# Optical_RX_TX_1-14.net
KiCad netlist of a schematic drawn in Altium Designer
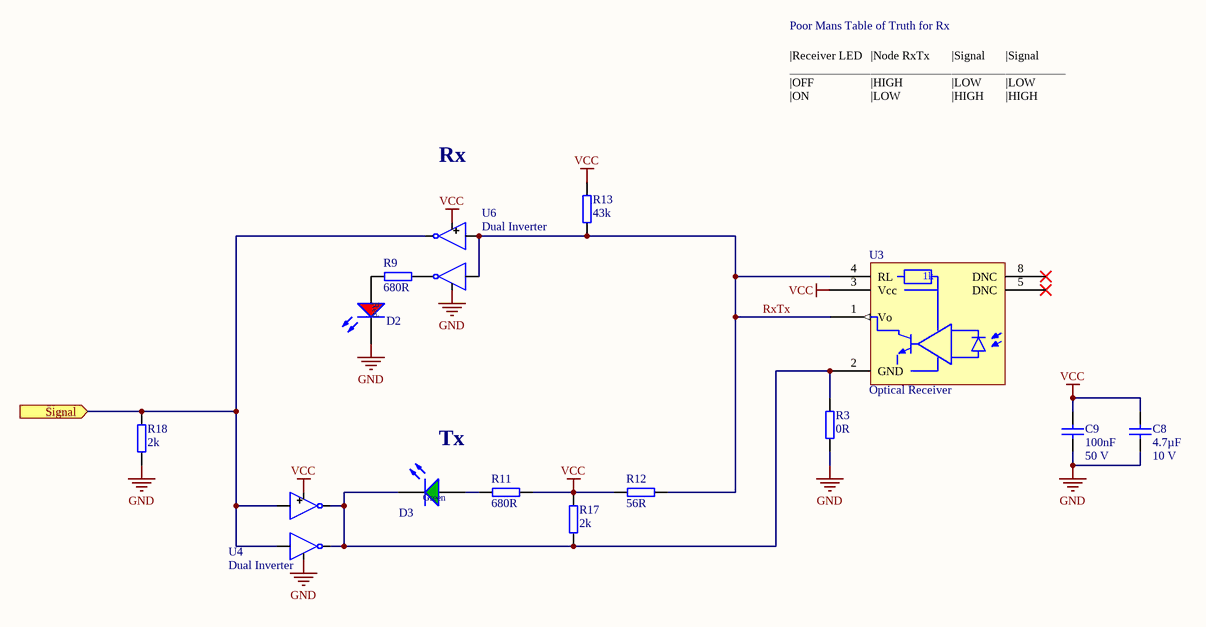
[diagram p0: Optical_RX_TX_1-14.SchDoc]

(export (version "E")
  (design (tool "Eeschema 10.0.6"))
  (components
    (comp (ref "C8")
      (value "4.7µF")
      (footprint "CAP_2012X06N")
      (description "CAP 0805 (2012 Metric) SMD")
      (fields
        (field (name "TOLERANCE") "±10%")
        (field (name "MF") "Taiyo Yuden")
        (field (name "VOLTAGE") "10 V")
        (field (name "CREATED") "2018_09_06_AGeiger")
      )
      (libsource (lib "UZOhm_Optical") (part "C_0805"))
    )
    (comp (ref "C9")
      (value "100nF")
      (footprint "C_0603(1608)100_L")
      (description "CAP 0603 (1608 Metric) SMD")
      (fields
        (field (name "TOLERANCE") "±5%")
        (field (name "LCSC PART #") "C14663")
        (field (name "RATED VOLTAGE") "50 V")
        (field (name "CREATED") "2018_09_06_AGeiger")
      )
      (libsource (lib "UZOhm_Optical") (part "C_0603"))
    )
    (comp (ref "D2")
      (value "150060RS75000")
      (footprint "WL-SMCW_0603")
      (description "WL-SMCW SMD Mono-color Chip LED Waterclear, size 0603, Red, 2 V, 140°")
      (fields
        (field (name "MF") "Wuerth Elektronik")
        (field (name "LCSC PART #") "C2286")
        (field (name "CREATED") "2018_09_06_AGeiger")
      )
      (libsource (lib "UZOhm_Optical") (part "LED_Red_0603"))
    )
    (comp (ref "D3")
      (value "150060GS75000")
      (footprint "WL-SMCW_0603")
      (description "WL-SMCW SMD Mono-color Chip LED Waterclear, size 0603, Green, 3.2 V, 140°")
      (fields
        (field (name "MF") "Wuerth Elektronik")
        (field (name "LCSC PART #") "C72043")
        (field (name "CREATED") "2018_09_06_AGeiger")
      )
      (libsource (lib "UZOhm_Optical") (part "LED_Green_0603"))
    )
    (comp (ref "R3")
      (value "0R")
      (footprint "R_0603_N")
      (description "SMD Resistor 0603")
      (fields
        (field (name "TOLERANCE") "1%")
        (field (name "VOLTAGE") "75V")
        (field (name "CREATED") "2018_09_06_AGeiger")
      )
      (libsource (lib "UZOhm_Optical") (part "R_0603"))
    )
    (comp (ref "R9")
      (value "680R")
      (footprint "R_0603_N")
      (description "SMD Resistor 0603")
      (fields
        (field (name "TOLERANCE") "1%")
        (field (name "VOLTAGE") "75V")
        (field (name "CREATED") "2018_09_06_AGeiger")
      )
      (libsource (lib "UZOhm_Optical") (part "R_0603"))
    )
    (comp (ref "R11")
      (value "680R")
      (footprint "R_0603_N")
      (description "SMD Resistor 0603")
      (fields
        (field (name "TOLERANCE") "1%")
        (field (name "VOLTAGE") "75V")
        (field (name "CREATED") "2018_09_06_AGeiger")
      )
      (libsource (lib "UZOhm_Optical") (part "R_0603"))
    )
    (comp (ref "R12")
      (value "56R")
      (footprint "RES_2012X06N")
      (description "SMD Resistor 0805")
      (fields (field (name "MF") "Bourns") (field (name "MPN") "CR0805-FX-1200ELF"))
      (libsource (lib "UZOhm_Optical") (part "R_0805"))
    )
    (comp (ref "R13")
      (value "43k")
      (footprint "R_0603_N")
      (description "SMD Resistor 0603")
      (fields
        (field (name "TOLERANCE") "1%")
        (field (name "VOLTAGE") "50V")
        (field (name "CREATED") "2018_09_06_AGeiger")
      )
      (libsource (lib "UZOhm_Optical") (part "R_0603_JLC"))
    )
    (comp (ref "R17")
      (value "2k")
      (footprint "R_0603_N")
      (description "SMD Resistor 0603")
      (fields
        (field (name "TOLERANCE") "1%")
        (field (name "VOLTAGE") "75 V")
        (field (name "CREATED") "2018_09_06_AGeiger")
      )
      (libsource (lib "UZOhm_Optical") (part "R_0603"))
    )
    (comp (ref "R18")
      (value "2k")
      (footprint "R_0603_N")
      (description "SMD Resistor 0603")
      (fields
        (field (name "TOLERANCE") "1%")
        (field (name "VOLTAGE") "75 V")
        (field (name "CREATED") "2018_09_06_AGeiger")
      )
      (libsource (lib "UZOhm_Optical") (part "R_0603"))
    )
    (comp (ref "U3")
      (value "Optical Receiver")
      (footprint "HFBRx5XX")
      (description "Fibre Optic Receivers, LINK HORIZ 5MBd RC VR RoHS")
      (fields
        (field (name "MF") "Boadcom/Avago")
        (field (name "MPN") "HFBR-2521Z")
        (field (name "CREATED") "2019_04_09_Kreppel")
      )
      (libsource (lib "UZOhm_Optical") (part "HFBR-2528Z"))
    )
    (comp (ref "U4")
      (value "Dual Inverter")
      (footprint "SN74LVC2GU04DCKR")
      (description "This dual inverter is designed for 1.65-V to 5.5-V VCC\r\noperation.")
      (fields (field (name "LCSC PART #") "C116660"))
      (libsource (lib "UZOhm_Optical") (part "SN74LVC2GU04DCKR"))
    )
    (comp (ref "U6")
      (value "Dual Inverter")
      (footprint "SN74LVC2GU04DCKR")
      (description "This dual inverter is designed for 1.65-V to 5.5-V VCC\r\noperation.")
      (fields (field (name "LCSC PART #") "C116660"))
      (libsource (lib "UZOhm_Optical") (part "SN74LVC2GU04DCKR"))
    )
  )
  (nets
    (net (code "1") (name "/RxTx") (class "Default")
      (node (ref "R12") (pin "2") (pintype "passive"))
      (node (ref "R13") (pin "2") (pinfunction "2_2") (pintype "passive"))
      (node (ref "U3") (pin "1") (pinfunction "Vo_1") (pintype "output"))
      (node (ref "U3") (pin "4") (pinfunction "RL_4") (pintype "passive"))
      (node (ref "U6") (pin "1") (pinfunction "IN1_1") (pintype "passive"))
      (node (ref "U6") (pin "3") (pinfunction "IN2_3") (pintype "passive"))
    )
    (net (code "2") (name "/Signal") (class "Default")
      (node (ref "R18") (pin "2") (pinfunction "2_2") (pintype "passive"))
      (node (ref "U4") (pin "1") (pinfunction "IN1_1") (pintype "passive"))
      (node (ref "U4") (pin "3") (pinfunction "IN2_3") (pintype "passive"))
      (node (ref "U6") (pin "6") (pinfunction "OUT2_6") (pintype "passive"))
    )
    (net (code "3") (name "GND") (class "Default")
      (node (ref "C8") (pin "2") (pinfunction "2_2") (pintype "passive"))
      (node (ref "C9") (pin "2") (pinfunction "2_2") (pintype "passive"))
      (node (ref "D2") (pin "1") (pinfunction "K_1") (pintype "passive"))
      (node (ref "R18") (pin "1") (pinfunction "1_1") (pintype "passive"))
      (node (ref "R3") (pin "2") (pinfunction "2_2") (pintype "passive"))
      (node (ref "U4") (pin "2") (pinfunction "GND_2") (pintype "passive"))
      (node (ref "U6") (pin "2") (pinfunction "GND_2") (pintype "passive"))
    )
    (net (code "4") (name "Net-(D2-A)") (class "Default")
      (node (ref "D2") (pin "2") (pinfunction "A_2") (pintype "passive"))
      (node (ref "R9") (pin "2") (pinfunction "2_2") (pintype "passive"))
    )
    (net (code "5") (name "Net-(D3-A)") (class "Default")
      (node (ref "D3") (pin "2") (pinfunction "A_2") (pintype "passive"))
      (node (ref "R11") (pin "2") (pinfunction "2_2") (pintype "passive"))
    )
    (net (code "6") (name "Net-(D3-K)") (class "Default")
      (node (ref "D3") (pin "1") (pinfunction "K_1") (pintype "passive"))
      (node (ref "R17") (pin "1") (pinfunction "1_1") (pintype "passive"))
      (node (ref "R3") (pin "1") (pinfunction "1_1") (pintype "passive"))
      (node (ref "U3") (pin "2") (pinfunction "GND_2") (pintype "power_in"))
      (node (ref "U4") (pin "4") (pinfunction "OUT2_4") (pintype "passive"))
      (node (ref "U4") (pin "6") (pinfunction "OUT2_6") (pintype "passive"))
    )
    (net (code "7") (name "Net-(R9-Pad1)") (class "Default")
      (node (ref "R9") (pin "1") (pinfunction "1_1") (pintype "passive"))
      (node (ref "U6") (pin "4") (pinfunction "OUT2_4") (pintype "passive"))
    )
    (net (code "8") (name "VCC") (class "Default")
      (node (ref "C8") (pin "1") (pinfunction "1_1") (pintype "passive"))
      (node (ref "C9") (pin "1") (pinfunction "1_1") (pintype "passive"))
      (node (ref "R11") (pin "1") (pinfunction "1_1") (pintype "passive"))
      (node (ref "R12") (pin "1") (pintype "passive"))
      (node (ref "R13") (pin "1") (pinfunction "1_1") (pintype "passive"))
      (node (ref "R17") (pin "2") (pinfunction "2_2") (pintype "passive"))
      (node (ref "U3") (pin "3") (pinfunction "Vcc_3") (pintype "power_in"))
      (node (ref "U4") (pin "5") (pinfunction "VCC_5") (pintype "passive"))
      (node (ref "U6") (pin "5") (pinfunction "VCC_5") (pintype "passive"))
    )
    (net (code "9") (name "unconnected-(U3-DNC-Pad5)") (class "Default")
      (node (ref "U3") (pin "5") (pinfunction "DNC_5") (pintype "passive+no_connect"))
    )
    (net (code "10") (name "unconnected-(U3-DNC-Pad8)") (class "Default")
      (node (ref "U3") (pin "8") (pinfunction "DNC_8") (pintype "passive+no_connect"))
    )
  )
)
